# design.net
KiCad netlist of a schematic drawn in EasyEDA Pro
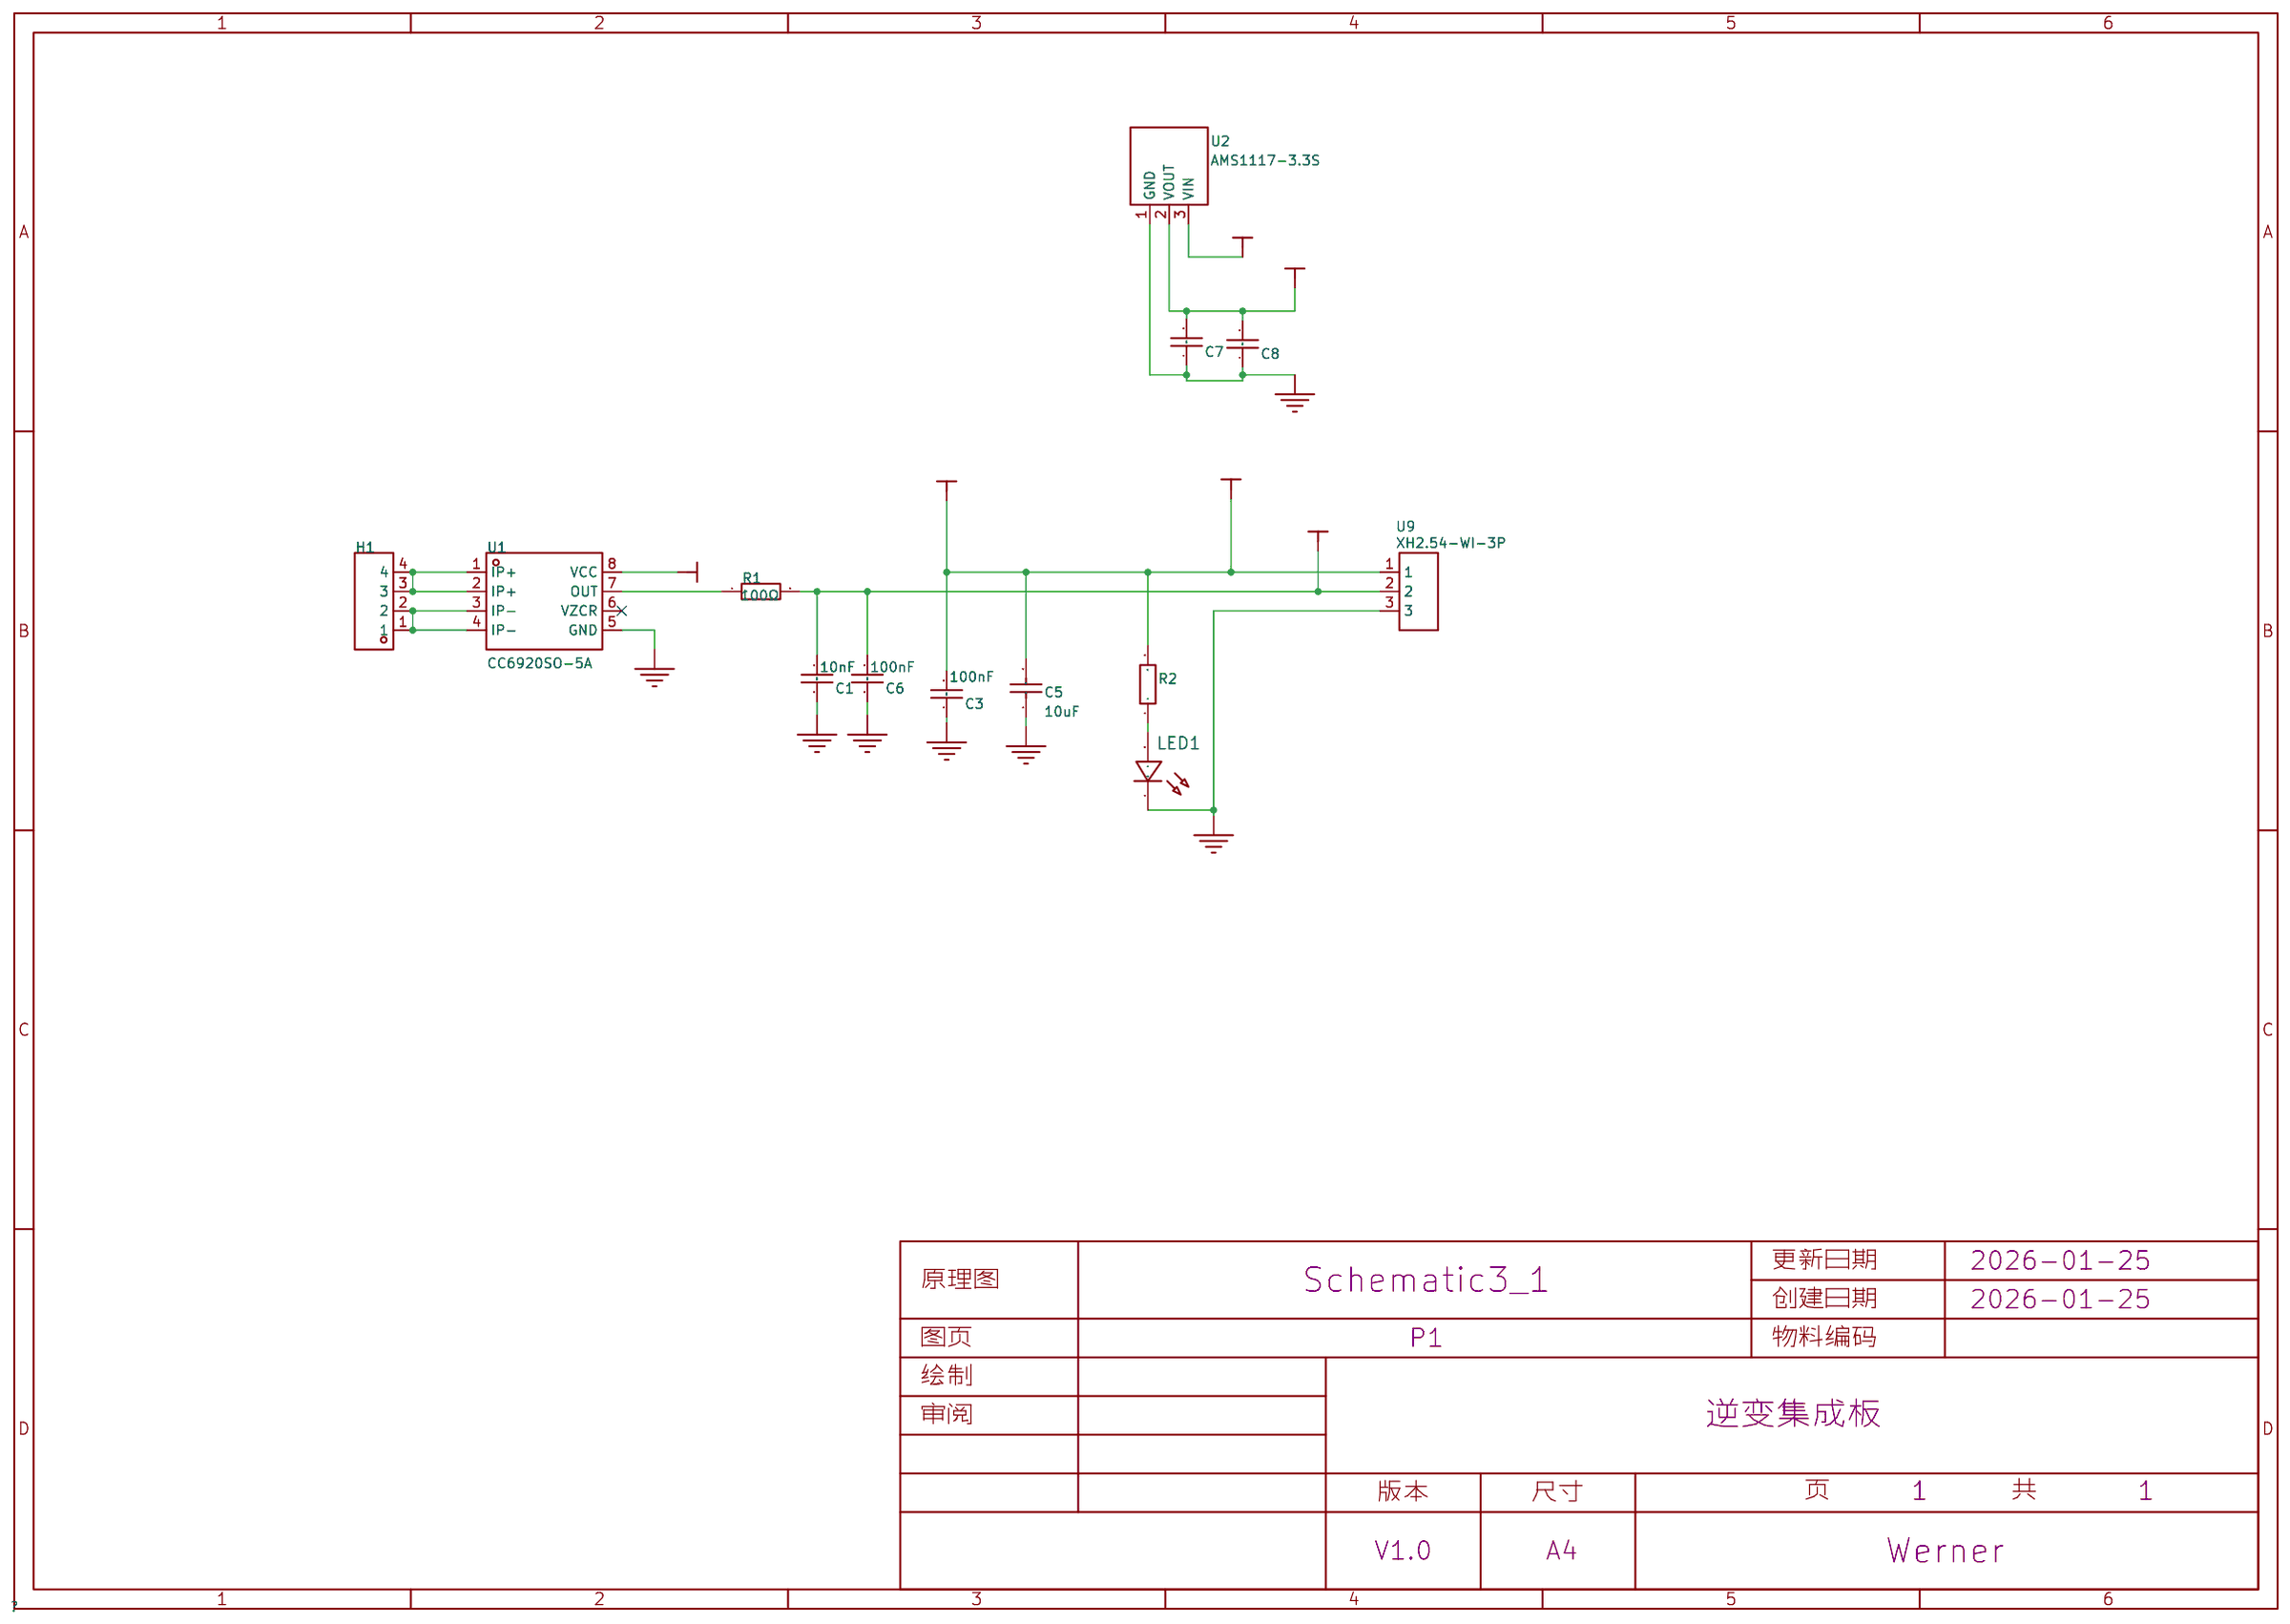
[diagram p0: schematic sheet]

(export (version "E")
  (design (tool "Eeschema 10.0.6"))
  (components
    (comp (ref "C1")
      (value "10nF")
      (footprint "easyedapro:C0603")
      (libsource (lib "easyedapro") (part "C0603"))
    )
    (comp (ref "C3")
      (value "100nF")
      (footprint "easyedapro:C0603")
      (libsource (lib "easyedapro") (part "C0603"))
    )
    (comp (ref "C5")
      (value "10uF")
      (footprint "easyedapro:C1206")
      (fields
        (field (name "Manufacturer Part") "CL31B104KBCNNNC")
        (field (name "Manufacturer") "SAMSUNG(三星)")
      )
      (libsource (lib "easyedapro") (part "C1206"))
    )
    (comp (ref "C6")
      (value "100nF")
      (footprint "easyedapro:C0603")
      (libsource (lib "easyedapro") (part "C0603"))
    )
    (comp (ref "C7") (value "~") (footprint "easyedapro:C0603") (libsource (lib "easyedapro") (part "C0603")))
    (comp (ref "C8") (value "~") (footprint "easyedapro:C0603") (libsource (lib "easyedapro") (part "C0603")))
    (comp (ref "H1")
      (value "PZ254V-11-04P")
      (footprint "easyedapro:HDR-TH_4P-P2.54-V-M")
      (fields (field (name "Manufacturer") "XFCN(兴飞)"))
      (libsource (lib "easyedapro") (part "PZ254V-11-04P"))
    )
    (comp (ref "LED1")
      (value "~")
      (footprint "easyedapro:LED_604")
      (libsource (lib "easyedapro") (part "LED_0603-R"))
    )
    (comp (ref "R1")
      (value "100Ω")
      (footprint "easyedapro:Res_0603")
      (libsource (lib "easyedapro") (part "R0603"))
    )
    (comp (ref "R2")
      (value "~")
      (footprint "easyedapro:Res_0603")
      (libsource (lib "easyedapro") (part "R0603"))
    )
    (comp (ref "U1")
      (value "CC6920SO-5A")
      (footprint "easyedapro:SOP-8_L4.9-W3.9-P1.27-LS6.0-BL")
      (fields (field (name "Manufacturer") "CrossChip(成都芯进)"))
      (libsource (lib "easyedapro") (part "CC6920SO-5A"))
    )
    (comp (ref "U2")
      (value "AMS1117-3.3S")
      (footprint "easyedapro:SOT-89-3_L4.5-W2.5-P1.50-LS4.2-BR")
      (fields (field (name "Manufacturer") "UMW(友台半导体)"))
      (libsource (lib "easyedapro") (part "AMS1117-3.3_C347256"))
    )
    (comp (ref "U9")
      (value "XH2.54-WI-3P")
      (footprint "easyedapro:CONN-TH_XH2.54-WI-3P")
      (libsource (lib "easyedapro") (part "XH2.54-WI-3P"))
    )
  )
  (nets
    (net (code "1") (name "3V3") (class "Default")
      (node (ref "C7") (pin "2") (pinfunction "2_2") (pintype "input"))
      (node (ref "C8") (pin "2") (pinfunction "2_2") (pintype "input"))
      (node (ref "U1") (pin "8") (pinfunction "VCC_8") (pintype "unspecified"))
      (node (ref "U2") (pin "2") (pinfunction "VOUT_2") (pintype "unspecified"))
    )
    (net (code "2") (name "5V") (class "Default")
      (node (ref "C3") (pin "2") (pinfunction "2_2") (pintype "input"))
      (node (ref "C5") (pin "2") (pinfunction "2_2") (pintype "input"))
      (node (ref "R2") (pin "2") (pinfunction "2_2") (pintype "input"))
      (node (ref "U2") (pin "3") (pinfunction "VIN_3") (pintype "unspecified"))
      (node (ref "U9") (pin "1") (pinfunction "1_1") (pintype "unspecified"))
    )
    (net (code "3") (name "GND") (class "Default")
      (node (ref "C1") (pin "1") (pinfunction "1_1") (pintype "input"))
      (node (ref "C3") (pin "1") (pinfunction "1_1") (pintype "input"))
      (node (ref "C5") (pin "1") (pinfunction "1_1") (pintype "input"))
      (node (ref "C6") (pin "1") (pinfunction "1_1") (pintype "input"))
      (node (ref "C7") (pin "1") (pinfunction "1_1") (pintype "input"))
      (node (ref "C8") (pin "1") (pinfunction "1_1") (pintype "input"))
      (node (ref "LED1") (pin "1") (pinfunction "C_1") (pintype "input"))
      (node (ref "U1") (pin "5") (pinfunction "GND_5") (pintype "unspecified"))
      (node (ref "U2") (pin "1") (pinfunction "GND_1") (pintype "unspecified"))
      (node (ref "U9") (pin "3") (pinfunction "3_3") (pintype "unspecified"))
    )
    (net (code "4") (name "Net-(H1-Pad1)") (class "Default")
      (node (ref "H1") (pin "1") (pinfunction "1_1") (pintype "unspecified"))
      (node (ref "H1") (pin "2") (pinfunction "2_2") (pintype "unspecified"))
      (node (ref "U1") (pin "3") (pinfunction "IP-_3") (pintype "unspecified"))
      (node (ref "U1") (pin "4") (pinfunction "IP-_4") (pintype "unspecified"))
    )
    (net (code "5") (name "Net-(H1-Pad3)") (class "Default")
      (node (ref "H1") (pin "3") (pinfunction "3_3") (pintype "unspecified"))
      (node (ref "H1") (pin "4") (pinfunction "4_4") (pintype "unspecified"))
      (node (ref "U1") (pin "1") (pinfunction "IP+_1") (pintype "unspecified"))
      (node (ref "U1") (pin "2") (pinfunction "IP+_2") (pintype "unspecified"))
    )
    (net (code "6") (name "Net-(LED1-A)") (class "Default")
      (node (ref "LED1") (pin "2") (pinfunction "A_2") (pintype "input"))
      (node (ref "R2") (pin "1") (pinfunction "1_1") (pintype "input"))
    )
    (net (code "7") (name "Net-(U1-OUT)") (class "Default")
      (node (ref "R1") (pin "1") (pinfunction "1_1") (pintype "input"))
      (node (ref "U1") (pin "7") (pinfunction "OUT_7") (pintype "unspecified"))
    )
    (net (code "8") (name "VOUT") (class "Default")
      (node (ref "C1") (pin "2") (pinfunction "2_2") (pintype "input"))
      (node (ref "C6") (pin "2") (pinfunction "2_2") (pintype "input"))
      (node (ref "R1") (pin "2") (pinfunction "2_2") (pintype "input"))
      (node (ref "U9") (pin "2") (pinfunction "2_2") (pintype "unspecified"))
    )
    (net (code "9") (name "unconnected-(U1-VZCR-Pad6)") (class "Default")
      (node (ref "U1") (pin "6") (pinfunction "VZCR_6") (pintype "unspecified+no_connect"))
    )
  )
)
